# SLG59H1120V_Breakout.net
KiCad netlist of a schematic drawn in EAGLE
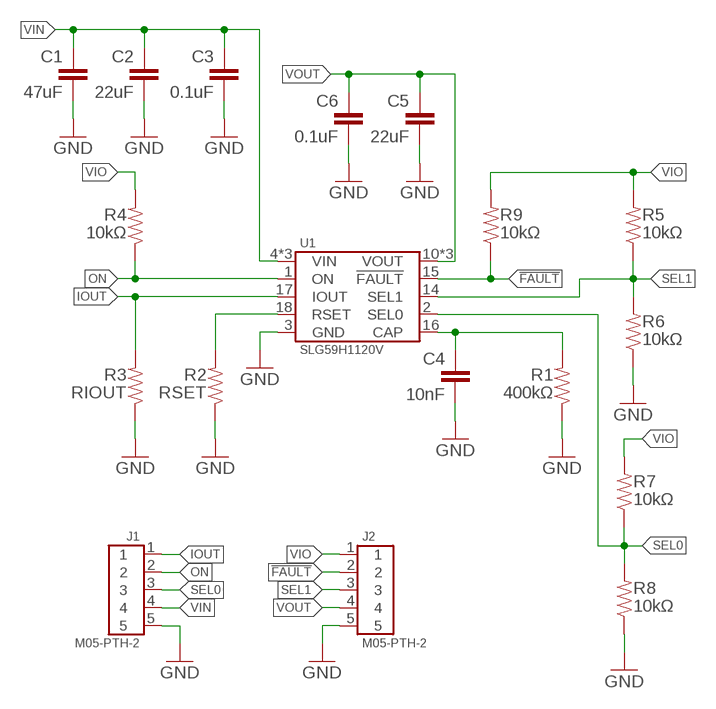
[diagram p0: schematic, sheet 1]

(export (version "E")
  (design (tool "Eeschema 10.0.6"))
  (components
    (comp (ref "C1")
      (value "47uF")
      (footprint "eagle-import:1206")
      (libsource (lib "eagle-import") (part "CAP-1206"))
    )
    (comp (ref "C2")
      (value "22uF")
      (footprint "eagle-import:1206")
      (libsource (lib "eagle-import") (part "CAP-1206"))
    )
    (comp (ref "C3")
      (value "0.1uF")
      (footprint "eagle-import:0603-CAP")
      (libsource (lib "eagle-import") (part "CAP-0603"))
    )
    (comp (ref "C4")
      (value "10nF")
      (footprint "eagle-import:0603-CAP")
      (libsource (lib "eagle-import") (part "CAP-0603"))
    )
    (comp (ref "C5")
      (value "22uF")
      (footprint "eagle-import:1206")
      (libsource (lib "eagle-import") (part "CAP-1206"))
    )
    (comp (ref "C6")
      (value "0.1uF")
      (footprint "eagle-import:0603-CAP")
      (libsource (lib "eagle-import") (part "CAP-0603"))
    )
    (comp (ref "J1")
      (value "M05-PTH-2")
      (footprint "eagle-import:M05-2")
      (libsource (lib "eagle-import") (part "M05-PTH-2"))
    )
    (comp (ref "J2")
      (value "M05-PTH-2")
      (footprint "eagle-import:M05-2")
      (libsource (lib "eagle-import") (part "M05-PTH-2"))
    )
    (comp (ref "R1")
      (value "400kΩ")
      (footprint "eagle-import:0603-CAP")
      (libsource (lib "eagle-import") (part "RESISTOR-0603"))
    )
    (comp (ref "R2")
      (value "RSET")
      (footprint "eagle-import:0603-CAP")
      (libsource (lib "eagle-import") (part "RESISTOR-0603"))
    )
    (comp (ref "R3")
      (value "RIOUT")
      (footprint "eagle-import:0603-CAP")
      (libsource (lib "eagle-import") (part "RESISTOR-0603"))
    )
    (comp (ref "R4")
      (value "10kΩ")
      (footprint "eagle-import:0603-CAP")
      (libsource (lib "eagle-import") (part "RESISTOR-0603"))
    )
    (comp (ref "R5")
      (value "10kΩ")
      (footprint "eagle-import:0603-CAP")
      (libsource (lib "eagle-import") (part "RESISTOR-0603"))
    )
    (comp (ref "R6")
      (value "10kΩ")
      (footprint "eagle-import:0603-CAP")
      (libsource (lib "eagle-import") (part "RESISTOR-0603"))
    )
    (comp (ref "R7")
      (value "10kΩ")
      (footprint "eagle-import:0603-CAP")
      (libsource (lib "eagle-import") (part "RESISTOR-0603"))
    )
    (comp (ref "R8")
      (value "10kΩ")
      (footprint "eagle-import:0603-CAP")
      (libsource (lib "eagle-import") (part "RESISTOR-0603"))
    )
    (comp (ref "R9")
      (value "10kΩ")
      (footprint "eagle-import:0603-CAP")
      (libsource (lib "eagle-import") (part "RESISTOR-0603"))
    )
    (comp (ref "U1")
      (value "SLG59H1120V")
      (footprint "eagle-import:STQFN-18-1.6X3")
      (libsource (lib "eagle-import") (part "SLG59H1120V"))
    )
  )
  (nets
    (net (code "1") (name "/~{FAULT}") (class "Default")
      (node (ref "J2") (pin "2") (pinfunction "2_2") (pintype "bidirectional"))
      (node (ref "R9") (pin "1") (pinfunction "1_1") (pintype "passive"))
      (node (ref "U1") (pin "15") (pinfunction "~{FAULT}_15") (pintype "bidirectional"))
    )
    (net (code "2") (name "GND") (class "Default")
      (node (ref "C1") (pin "2") (pinfunction "2_2") (pintype "passive"))
      (node (ref "C2") (pin "2") (pinfunction "2_2") (pintype "passive"))
      (node (ref "C3") (pin "2") (pinfunction "2_2") (pintype "passive"))
      (node (ref "C4") (pin "2") (pinfunction "2_2") (pintype "passive"))
      (node (ref "C5") (pin "2") (pinfunction "2_2") (pintype "passive"))
      (node (ref "C6") (pin "2") (pinfunction "2_2") (pintype "passive"))
      (node (ref "J1") (pin "5") (pinfunction "5_5") (pintype "bidirectional"))
      (node (ref "J2") (pin "5") (pinfunction "5_5") (pintype "bidirectional"))
      (node (ref "R1") (pin "1") (pinfunction "1_1") (pintype "passive"))
      (node (ref "R2") (pin "1") (pinfunction "1_1") (pintype "passive"))
      (node (ref "R3") (pin "1") (pinfunction "1_1") (pintype "passive"))
      (node (ref "R6") (pin "1") (pinfunction "1_1") (pintype "passive"))
      (node (ref "R8") (pin "1") (pinfunction "1_1") (pintype "passive"))
      (node (ref "U1") (pin "3") (pinfunction "GND_3") (pintype "bidirectional"))
    )
    (net (code "3") (name "IOUT") (class "Default")
      (node (ref "J1") (pin "1") (pinfunction "1_1") (pintype "bidirectional"))
      (node (ref "R3") (pin "2") (pinfunction "2_2") (pintype "passive"))
      (node (ref "U1") (pin "17") (pinfunction "IOUT_17") (pintype "bidirectional"))
    )
    (net (code "4") (name "Net-(U1-CAP)") (class "Default")
      (node (ref "C4") (pin "1") (pinfunction "1_1") (pintype "passive"))
      (node (ref "R1") (pin "2") (pinfunction "2_2") (pintype "passive"))
      (node (ref "U1") (pin "16") (pinfunction "CAP_16") (pintype "bidirectional"))
    )
    (net (code "5") (name "Net-(U1-RSET)") (class "Default")
      (node (ref "R2") (pin "2") (pinfunction "2_2") (pintype "passive"))
      (node (ref "U1") (pin "18") (pinfunction "RSET_18") (pintype "bidirectional"))
    )
    (net (code "6") (name "ON") (class "Default")
      (node (ref "J1") (pin "2") (pinfunction "2_2") (pintype "bidirectional"))
      (node (ref "R4") (pin "1") (pinfunction "1_1") (pintype "passive"))
      (node (ref "U1") (pin "1") (pinfunction "ON_1") (pintype "bidirectional"))
    )
    (net (code "7") (name "SEL0") (class "Default")
      (node (ref "J1") (pin "3") (pinfunction "3_3") (pintype "bidirectional"))
      (node (ref "R7") (pin "1") (pinfunction "1_1") (pintype "passive"))
      (node (ref "R8") (pin "2") (pinfunction "2_2") (pintype "passive"))
      (node (ref "U1") (pin "2") (pinfunction "SEL0_2") (pintype "bidirectional"))
    )
    (net (code "8") (name "SEL1") (class "Default")
      (node (ref "J2") (pin "3") (pinfunction "3_3") (pintype "bidirectional"))
      (node (ref "R5") (pin "1") (pinfunction "1_1") (pintype "passive"))
      (node (ref "R6") (pin "2") (pinfunction "2_2") (pintype "passive"))
      (node (ref "U1") (pin "14") (pinfunction "SEL1_14") (pintype "bidirectional"))
    )
    (net (code "9") (name "VIN") (class "Default")
      (node (ref "C1") (pin "1") (pinfunction "1_1") (pintype "passive"))
      (node (ref "C2") (pin "1") (pinfunction "1_1") (pintype "passive"))
      (node (ref "C3") (pin "1") (pinfunction "1_1") (pintype "passive"))
      (node (ref "J1") (pin "4") (pinfunction "4_4") (pintype "bidirectional"))
      (node (ref "U1") (pin "4") (pinfunction "VIN_4") (pintype "bidirectional"))
      (node (ref "U1") (pin "5") (pinfunction "VIN_5") (pintype "bidirectional"))
      (node (ref "U1") (pin "6") (pinfunction "VIN_6") (pintype "bidirectional"))
    )
    (net (code "10") (name "VIO") (class "Default")
      (node (ref "J2") (pin "1") (pinfunction "1_1") (pintype "bidirectional"))
      (node (ref "R4") (pin "2") (pinfunction "2_2") (pintype "passive"))
      (node (ref "R5") (pin "2") (pinfunction "2_2") (pintype "passive"))
      (node (ref "R7") (pin "2") (pinfunction "2_2") (pintype "passive"))
      (node (ref "R9") (pin "2") (pinfunction "2_2") (pintype "passive"))
    )
    (net (code "11") (name "VOUT") (class "Default")
      (node (ref "C5") (pin "1") (pinfunction "1_1") (pintype "passive"))
      (node (ref "C6") (pin "1") (pinfunction "1_1") (pintype "passive"))
      (node (ref "J2") (pin "4") (pinfunction "4_4") (pintype "bidirectional"))
      (node (ref "U1") (pin "10") (pinfunction "VOUT_10") (pintype "bidirectional"))
      (node (ref "U1") (pin "11") (pinfunction "VOUT_11") (pintype "bidirectional"))
      (node (ref "U1") (pin "12") (pinfunction "VOUT_12") (pintype "bidirectional"))
    )
  )
)
